# MicroUSB.net
KiCad netlist of a schematic drawn in Altium Designer
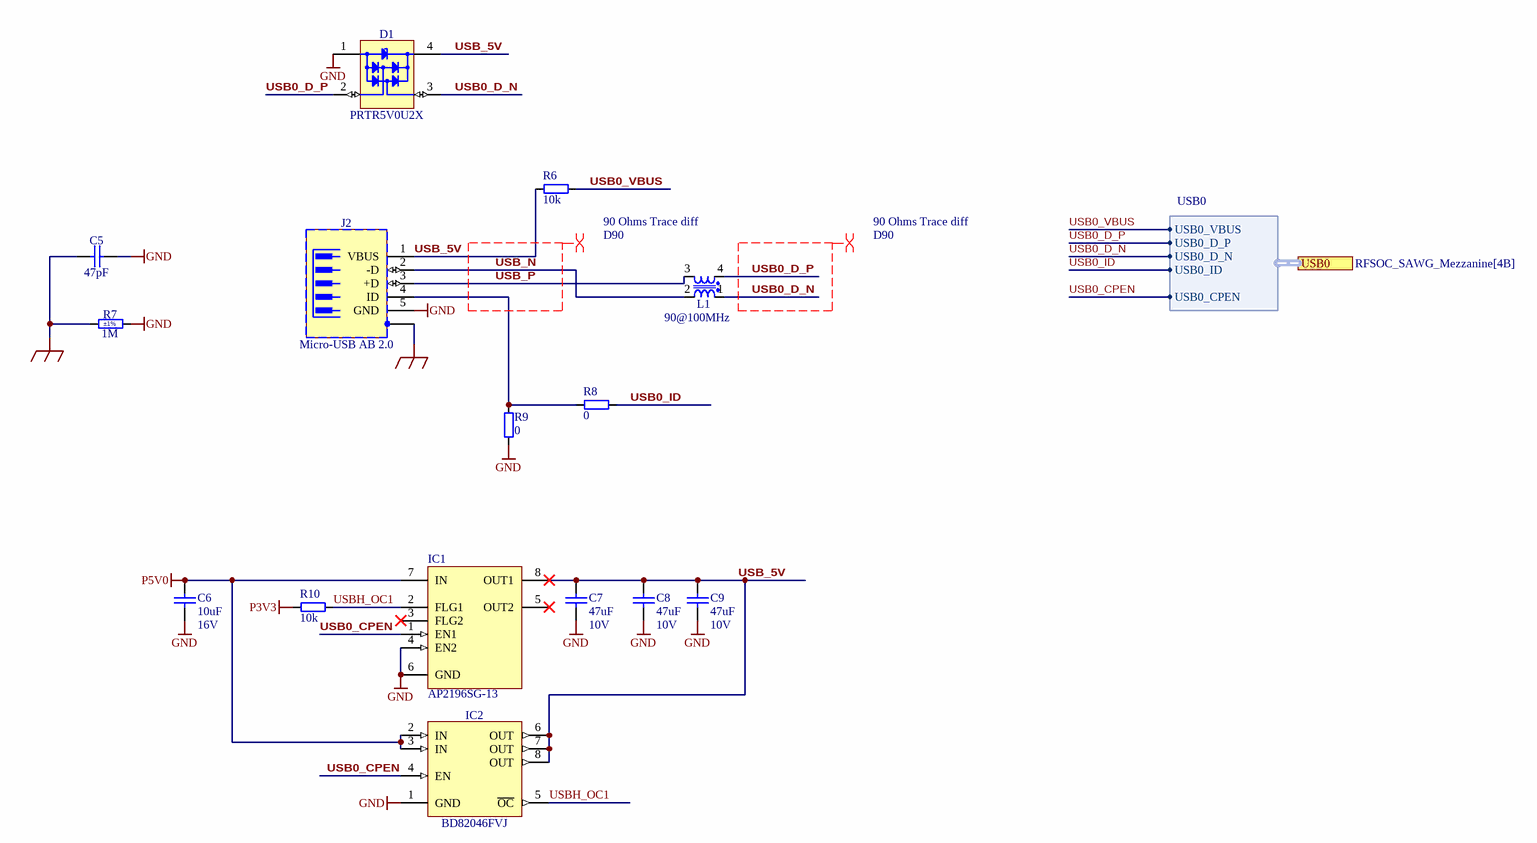
[diagram p0: MicroUSB.SchDoc]

(export (version "E")
  (design (tool "Eeschema 10.0.6"))
  (components
    (comp (ref "C5")
      (value "47pF")
      (footprint "CAPC3216X140N")
      (description "Non-polarised capacitor")
      (fields
        (field (name "PART NUMBER") "CC1206_47PF_1KV_10%_C0G")
        (field (name "VOLTAGE") "1KV")
        (field (name "AUTHOR") "CERN DEM BC")
      )
      (libsource (lib "Capacitors") (part "Capacitor - non polarized"))
    )
    (comp (ref "C6")
      (value "10uF")
      (footprint "CAPC1608X80N")
      (description "Non-polarised capacitor")
      (fields
        (field (name "VOLTAGE") "16V")
        (field (name "TOLERANCE") "±20%")
        (field (name "PART NUMBER") "CC0603_10UF_16V_20%_X5R")
        (field (name "AUTHOR") "CERN DEM MR")
      )
      (libsource (lib "Capacitors") (part "Capacitor - non polarized"))
    )
    (comp (ref "C7")
      (value "47uF")
      (footprint "CAPC3216X180N")
      (description "Non-polarised capacitor")
      (fields
        (field (name "VOLTAGE") "10V")
        (field (name "TOLERANCE") "±10%")
        (field (name "PART NUMBER") "CC1206_47UF_10V_10%_X5R")
        (field (name "AUTHOR") "CERN DEM MR")
      )
      (libsource (lib "Capacitors") (part "Capacitor - non polarized"))
    )
    (comp (ref "C8")
      (value "47uF")
      (footprint "CAPC3216X180N")
      (description "Non-polarised capacitor")
      (fields
        (field (name "VOLTAGE") "10V")
        (field (name "TOLERANCE") "±10%")
        (field (name "PART NUMBER") "CC1206_47UF_10V_10%_X5R")
        (field (name "AUTHOR") "CERN DEM MR")
      )
      (libsource (lib "Capacitors") (part "Capacitor - non polarized"))
    )
    (comp (ref "C9")
      (value "47uF")
      (footprint "CAPC3216X180N")
      (description "Non-polarised capacitor")
      (fields
        (field (name "VOLTAGE") "10V")
        (field (name "TOLERANCE") "±10%")
        (field (name "PART NUMBER") "CC1206_47UF_10V_10%_X5R")
        (field (name "AUTHOR") "CERN DEM MR")
      )
      (libsource (lib "Capacitors") (part "Capacitor - non polarized"))
    )
    (comp (ref "D1")
      (value "PRTR5V0U2X")
      (footprint "SOT190P230X110-4N")
      (description "Ultra Low Capacitance Double Rail-to-Rail ESD Protection Diode")
      (fields
        (field (name "VOLTAGE") "5.5V")
        (field (name "MANUFACTURER") "NXP SEMICONDUCTORS")
        (field (name "AUTHOR") "CERN DEM JLC")
      )
      (libsource (lib "ICs And Semiconductors") (part "PRTR5V0U2X"))
    )
    (comp (ref "IC1")
      (value "AP2196SG-13")
      (footprint "SOIC127P600X175-8N")
      (libsource (lib "TE") (part "AP2196"))
    )
    (comp (ref "IC2")
      (value "BD82046FVJ")
      (footprint "SOP65P490X110-8N")
      (description "3.2A Current Limit High Side Switch IC")
      (fields (field (name "MANUFACTURER") "ROHM") (field (name "AUTHOR") "CERN DEM BC"))
      (libsource (lib "ICs And Semiconductors") (part "BD82046FVJ"))
    )
    (comp (ref "J2")
      (value "Micro-USB AB 2.0")
      (footprint "HIROSE_ZX62RD-AB-5P8")
      (description "5 Pin + 1 Shield USB Receptacle")
      (fields
        (field (name "PART NUMBER") "HIROSE_ZX62RD-AB-5P8")
        (field (name "MANUFACTURER") "HIROSE (HRS)")
        (field (name "AUTHOR") "CERN DEM JLC")
      )
      (libsource (lib "Connectors") (part "Connector USB 5 Pin + 1Shield"))
    )
    (comp (ref "L1")
      (value "90@100MHz")
      (footprint "IND_WURTH_WE-CNSW_0504")
      (description "Inductor Common Mode")
      (fields
        (field (name "PART NUMBER") "IND0504_WURTH_7442335900")
        (field (name "POWER") "500mA")
        (field (name "AUTHOR") "CERN DEM JMW")
      )
      (libsource (lib "Inductors & Transformers") (part "Inductor Common Mode 1Dot-2 4Dot-3"))
    )
    (comp (ref "R6")
      (value "10k")
      (footprint "RESC1005X40N")
      (description "Resistor - 1%")
      (fields
        (field (name "TOLERANCE") "±1%")
        (field (name "PART NUMBER") "R0402_10K_1%_0.0625W_100PPM")
        (field (name "AUTHOR") "CERN DEM JLC")
      )
      (libsource (lib "Resistors") (part "Resistor - 1%"))
    )
    (comp (ref "R7")
      (value "1M")
      (footprint "RESC3216X65N")
      (description "Resistor - 1%")
      (fields
        (field (name "TOLERANCE") "±1%")
        (field (name "PART NUMBER") "R1206_1M_1%_0.25W_100PPM")
        (field (name "POWER") "0.25W")
        (field (name "AUTHOR") "CERN DEM JLC")
      )
      (libsource (lib "Resistors") (part "Resistor - 1%"))
    )
    (comp (ref "R8")
      (value "0")
      (footprint "RESC1005X40N")
      (description "Resistor")
      (fields
        (field (name "PART NUMBER") "R0402_0R_JUMPER")
        (field (name "MANUFACTURER") "GENERIC")
        (field (name "AUTHOR") "CERN DEM JLC")
      )
      (libsource (lib "Resistors") (part "Resistor"))
    )
    (comp (ref "R9")
      (value "0")
      (footprint "RESC1005X40N")
      (description "Resistor")
      (fields
        (field (name "PART NUMBER") "R0402_0R_JUMPER")
        (field (name "MANUFACTURER") "GENERIC")
        (field (name "AUTHOR") "CERN DEM JLC")
      )
      (libsource (lib "Resistors") (part "Resistor"))
    )
    (comp (ref "R10")
      (value "10k")
      (footprint "RESC1005X40N")
      (description "Resistor - 1%")
      (fields
        (field (name "TOLERANCE") "±1%")
        (field (name "PART NUMBER") "R0402_10K_1%_0.0625W_100PPM")
        (field (name "AUTHOR") "CERN DEM JLC")
      )
      (libsource (lib "Resistors") (part "Resistor - 1%"))
    )
  )
  (nets
    (net (code "2") (name "/USB0_CPEN") (class "Default")
      (node (ref "IC1") (pin "1") (pinfunction "EN1_1") (pintype "input"))
      (node (ref "IC2") (pin "4") (pinfunction "EN_4") (pintype "input"))
    )
    (net (code "3") (name "/USB0_D_N") (class "Default")
      (node (ref "D1") (pin "3") (pinfunction "I/O2_3") (pintype "bidirectional"))
      (node (ref "L1") (pin "1") (pinfunction "1_1") (pintype "passive"))
    )
    (net (code "4") (name "/USB0_D_P") (class "Default")
      (node (ref "D1") (pin "2") (pinfunction "I/O1_2") (pintype "bidirectional"))
      (node (ref "L1") (pin "4") (pinfunction "4_4") (pintype "passive"))
    )
    (net (code "5") (name "/USB0_ID") (class "Default")
      (node (ref "R8") (pin "2") (pinfunction "2_2") (pintype "passive"))
    )
    (net (code "6") (name "/USB0_VBUS") (class "Default")
      (node (ref "R6") (pin "2") (pinfunction "2_2") (pintype "passive"))
    )
    (net (code "7") (name "/USBH_OC1") (class "Default")
      (node (ref "IC1") (pin "2") (pinfunction "FLG1_2") (pintype "passive"))
      (node (ref "IC2") (pin "5") (pinfunction "~{OC}_5") (pintype "output"))
      (node (ref "R10") (pin "2") (pinfunction "2_2") (pintype "passive"))
    )
    (net (code "8") (name "/USB_5V") (class "Default")
      (node (ref "C7") (pin "1") (pinfunction "1_1") (pintype "passive"))
      (node (ref "C8") (pin "2") (pinfunction "2_2") (pintype "passive"))
      (node (ref "C9") (pin "2") (pinfunction "2_2") (pintype "passive"))
      (node (ref "D1") (pin "4") (pinfunction "VCC_4") (pintype "power_in"))
      (node (ref "IC1") (pin "8") (pinfunction "OUT1_8") (pintype "power_in"))
      (node (ref "IC2") (pin "6") (pinfunction "OUT_6") (pintype "output"))
      (node (ref "IC2") (pin "7") (pinfunction "OUT_7") (pintype "output"))
      (node (ref "IC2") (pin "8") (pinfunction "OUT_8") (pintype "output"))
      (node (ref "J2") (pin "1") (pinfunction "VBUS_1") (pintype "power_in"))
      (node (ref "R6") (pin "1") (pinfunction "1_1") (pintype "passive"))
    )
    (net (code "9") (name "/USB_N") (class "Default")
      (node (ref "J2") (pin "2") (pinfunction "-D_2") (pintype "bidirectional"))
      (node (ref "L1") (pin "2") (pinfunction "2_2") (pintype "passive"))
    )
    (net (code "10") (name "/USB_P") (class "Default")
      (node (ref "J2") (pin "3") (pinfunction "+D_3") (pintype "bidirectional"))
      (node (ref "L1") (pin "3") (pinfunction "3_3") (pintype "passive"))
    )
    (net (code "12") (name "FGND") (class "Default")
      (node (ref "C5") (pin "1") (pinfunction "1_1") (pintype "passive"))
      (node (ref "J2") (pin "6") (pinfunction "SH_6") (pintype "power_in"))
      (node (ref "R7") (pin "1") (pinfunction "1_1") (pintype "passive"))
    )
    (net (code "13") (name "GND") (class "Default")
      (node (ref "C5") (pin "2") (pinfunction "2_2") (pintype "passive"))
      (node (ref "C6") (pin "2") (pinfunction "2_2") (pintype "passive"))
      (node (ref "C7") (pin "2") (pinfunction "2_2") (pintype "passive"))
      (node (ref "C8") (pin "1") (pinfunction "1_1") (pintype "passive"))
      (node (ref "C9") (pin "1") (pinfunction "1_1") (pintype "passive"))
      (node (ref "D1") (pin "1") (pinfunction "GND_1") (pintype "power_in"))
      (node (ref "IC1") (pin "4") (pinfunction "EN2_4") (pintype "input"))
      (node (ref "IC1") (pin "6") (pinfunction "GND_6") (pintype "power_in"))
      (node (ref "IC2") (pin "1") (pinfunction "GND_1") (pintype "power_in"))
      (node (ref "J2") (pin "5") (pinfunction "GND_5") (pintype "power_in"))
      (node (ref "R7") (pin "2") (pinfunction "2_2") (pintype "passive"))
      (node (ref "R9") (pin "1") (pinfunction "1_1") (pintype "passive"))
    )
    (net (code "14") (name "Net-(J2-ID)") (class "Default")
      (node (ref "J2") (pin "4") (pinfunction "ID_4") (pintype "passive"))
      (node (ref "R8") (pin "1") (pinfunction "1_1") (pintype "passive"))
      (node (ref "R9") (pin "2") (pinfunction "2_2") (pintype "passive"))
    )
    (net (code "15") (name "P3V3") (class "Default")
      (node (ref "R10") (pin "1") (pinfunction "1_1") (pintype "passive"))
    )
    (net (code "16") (name "P5V0") (class "Default")
      (node (ref "C6") (pin "1") (pinfunction "1_1") (pintype "passive"))
      (node (ref "IC1") (pin "7") (pinfunction "IN_7") (pintype "power_in"))
      (node (ref "IC2") (pin "2") (pinfunction "IN_2") (pintype "input"))
      (node (ref "IC2") (pin "3") (pinfunction "IN_3") (pintype "input"))
    )
    (net (code "17") (name "unconnected-(IC1-FLG2-Pad3)") (class "Default")
      (node (ref "IC1") (pin "3") (pinfunction "FLG2_3") (pintype "passive+no_connect"))
    )
    (net (code "18") (name "unconnected-(IC1-OUT2-Pad5)") (class "Default")
      (node (ref "IC1") (pin "5") (pinfunction "OUT2_5") (pintype "power_in+no_connect"))
    )
  )
)
